# AutoSpiel.net
KiCad netlist of a schematic drawn in EAGLE
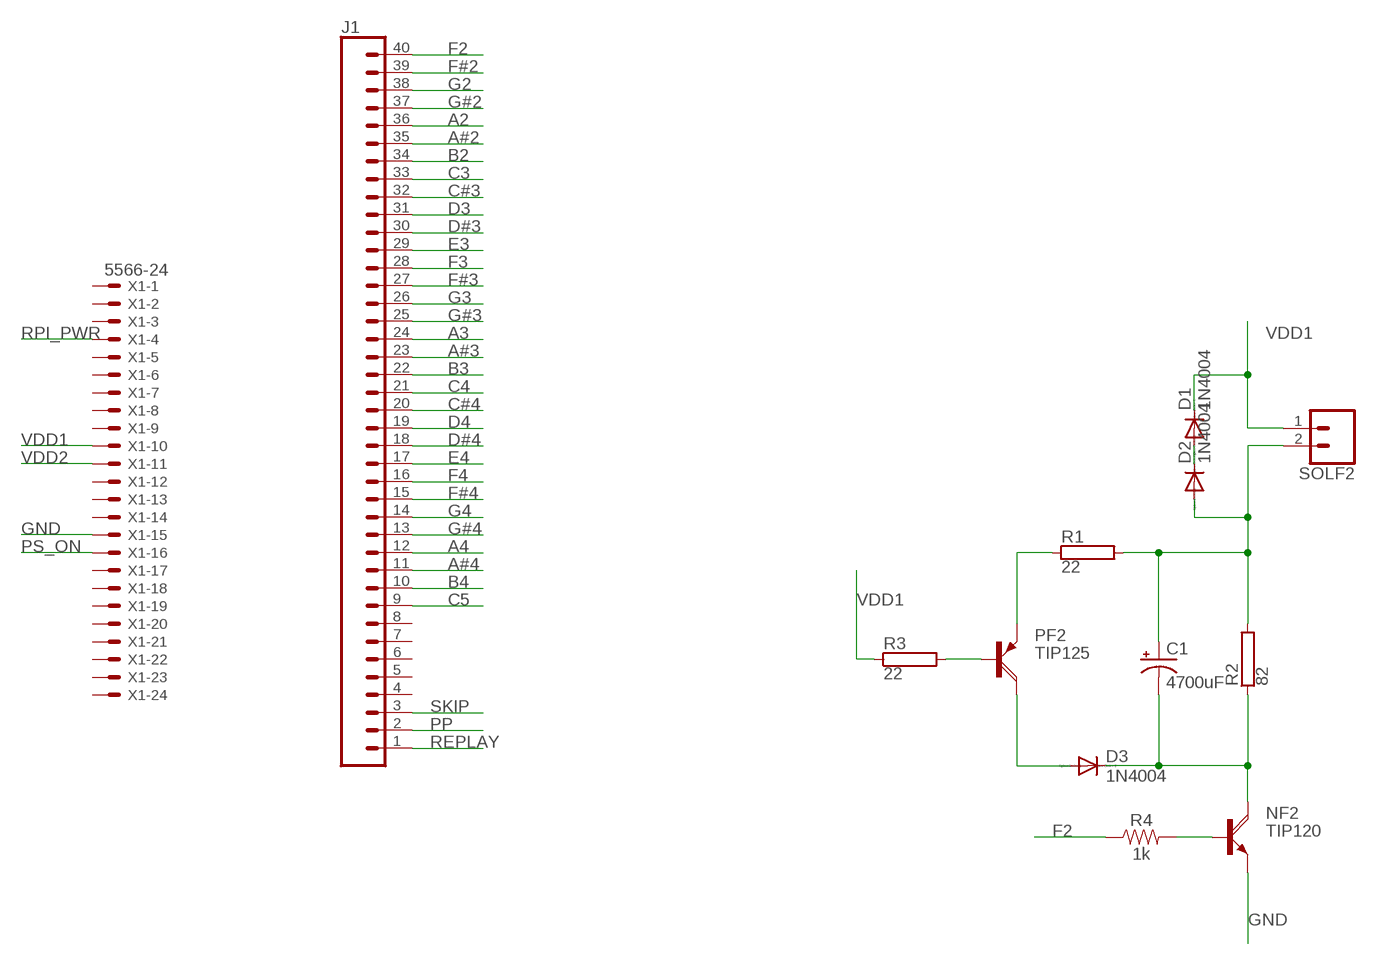
[diagram p0: schematic, sheet 1]

(export (version "E")
  (design (tool "Eeschema 10.0.6"))
  (components
    (comp (ref "C1")
      (value "4700uF")
      (footprint "eagle-import:E5-13")
      (libsource (lib "eagle-import") (part "CPOL-USE5-13"))
    )
    (comp (ref "D1")
      (value "1N4004")
      (footprint "eagle-import:DO41-10")
      (libsource (lib "eagle-import") (part "1N4004"))
    )
    (comp (ref "D2")
      (value "1N4004")
      (footprint "eagle-import:DO41-10")
      (libsource (lib "eagle-import") (part "1N4004"))
    )
    (comp (ref "D3")
      (value "1N4004")
      (footprint "eagle-import:DO41-10")
      (libsource (lib "eagle-import") (part "1N4004"))
    )
    (comp (ref "J1")
      (value "CONN_40")
      (footprint "eagle-import:1X40")
      (libsource (lib "eagle-import") (part "CONN_40"))
    )
    (comp (ref "NF2")
      (value "TIP120")
      (footprint "eagle-import:TO220AH")
      (libsource (lib "eagle-import") (part "TIP120"))
    )
    (comp (ref "PF2")
      (value "TIP125")
      (footprint "eagle-import:TO220AH")
      (libsource (lib "eagle-import") (part "TIP125"))
    )
    (comp (ref "R1")
      (value "22")
      (footprint "eagle-import:AC01")
      (libsource (lib "eagle-import") (part "RAC01"))
    )
    (comp (ref "R2")
      (value "82")
      (footprint "eagle-import:AC01")
      (libsource (lib "eagle-import") (part "RAC01"))
    )
    (comp (ref "R3")
      (value "22")
      (footprint "eagle-import:AC01")
      (libsource (lib "eagle-import") (part "RAC01"))
    )
    (comp (ref "R4")
      (value "1k")
      (footprint "eagle-import:AXIAL-0.3-KIT")
      (libsource (lib "eagle-import") (part "1KOHM-HORIZ_KIT-1/4W-5%"))
    )
    (comp (ref "SOLF2")
      (value "CONN_02PTH4")
      (footprint "eagle-import:1X02_XTRA_BIG")
      (libsource (lib "eagle-import") (part "CONN_02PTH4"))
    )
    (comp (ref "X1")
      (value "5566-24")
      (footprint "eagle-import:5566-24")
      (fields (field (name "MF") "MOLEX"))
      (libsource (lib "eagle-import") (part "5566-24"))
    )
  )
  (nets
    (net (code "1") (name "/A#2") (class "Default")
      (node (ref "J1") (pin "35") (pinfunction "35_35") (pintype "passive"))
    )
    (net (code "2") (name "/A#3") (class "Default")
      (node (ref "J1") (pin "23") (pinfunction "23_23") (pintype "passive"))
    )
    (net (code "3") (name "/A#4") (class "Default")
      (node (ref "J1") (pin "11") (pinfunction "11_11") (pintype "passive"))
    )
    (net (code "4") (name "/A2") (class "Default")
      (node (ref "J1") (pin "36") (pinfunction "36_36") (pintype "passive"))
    )
    (net (code "5") (name "/A3") (class "Default")
      (node (ref "J1") (pin "24") (pinfunction "24_24") (pintype "passive"))
    )
    (net (code "6") (name "/A4") (class "Default")
      (node (ref "J1") (pin "12") (pinfunction "12_12") (pintype "passive"))
    )
    (net (code "7") (name "/B2") (class "Default")
      (node (ref "J1") (pin "34") (pinfunction "34_34") (pintype "passive"))
    )
    (net (code "8") (name "/B3") (class "Default")
      (node (ref "J1") (pin "22") (pinfunction "22_22") (pintype "passive"))
    )
    (net (code "9") (name "/B4") (class "Default")
      (node (ref "J1") (pin "10") (pinfunction "10_10") (pintype "passive"))
    )
    (net (code "10") (name "/C#3") (class "Default")
      (node (ref "J1") (pin "32") (pinfunction "32_32") (pintype "passive"))
    )
    (net (code "11") (name "/C#4") (class "Default")
      (node (ref "J1") (pin "20") (pinfunction "20_20") (pintype "passive"))
    )
    (net (code "12") (name "/C3") (class "Default")
      (node (ref "J1") (pin "33") (pinfunction "33_33") (pintype "passive"))
    )
    (net (code "13") (name "/C4") (class "Default")
      (node (ref "J1") (pin "21") (pinfunction "21_21") (pintype "passive"))
    )
    (net (code "14") (name "/C5") (class "Default")
      (node (ref "J1") (pin "9") (pinfunction "9_9") (pintype "passive"))
    )
    (net (code "15") (name "/D#3") (class "Default")
      (node (ref "J1") (pin "30") (pinfunction "30_30") (pintype "passive"))
    )
    (net (code "16") (name "/D#4") (class "Default")
      (node (ref "J1") (pin "18") (pinfunction "18_18") (pintype "passive"))
    )
    (net (code "17") (name "/D3") (class "Default")
      (node (ref "J1") (pin "31") (pinfunction "31_31") (pintype "passive"))
    )
    (net (code "18") (name "/D4") (class "Default")
      (node (ref "J1") (pin "19") (pinfunction "19_19") (pintype "passive"))
    )
    (net (code "19") (name "/E3") (class "Default")
      (node (ref "J1") (pin "29") (pinfunction "29_29") (pintype "passive"))
    )
    (net (code "20") (name "/E4") (class "Default")
      (node (ref "J1") (pin "17") (pinfunction "17_17") (pintype "passive"))
    )
    (net (code "21") (name "/F#2") (class "Default")
      (node (ref "J1") (pin "39") (pinfunction "39_39") (pintype "passive"))
    )
    (net (code "22") (name "/F#3") (class "Default")
      (node (ref "J1") (pin "27") (pinfunction "27_27") (pintype "passive"))
    )
    (net (code "23") (name "/F#4") (class "Default")
      (node (ref "J1") (pin "15") (pinfunction "15_15") (pintype "passive"))
    )
    (net (code "24") (name "/F2") (class "Default")
      (node (ref "J1") (pin "40") (pinfunction "40_40") (pintype "passive"))
      (node (ref "R4") (pin "P$1") (pinfunction "1_P$1") (pintype "passive"))
    )
    (net (code "25") (name "/F3") (class "Default")
      (node (ref "J1") (pin "28") (pinfunction "28_28") (pintype "passive"))
    )
    (net (code "26") (name "/F4") (class "Default")
      (node (ref "J1") (pin "16") (pinfunction "16_16") (pintype "passive"))
    )
    (net (code "27") (name "/G#2") (class "Default")
      (node (ref "J1") (pin "37") (pinfunction "37_37") (pintype "passive"))
    )
    (net (code "28") (name "/G#3") (class "Default")
      (node (ref "J1") (pin "25") (pinfunction "25_25") (pintype "passive"))
    )
    (net (code "29") (name "/G#4") (class "Default")
      (node (ref "J1") (pin "13") (pinfunction "13_13") (pintype "passive"))
    )
    (net (code "30") (name "/G2") (class "Default")
      (node (ref "J1") (pin "38") (pinfunction "38_38") (pintype "passive"))
    )
    (net (code "31") (name "/G3") (class "Default")
      (node (ref "J1") (pin "26") (pinfunction "26_26") (pintype "passive"))
    )
    (net (code "32") (name "/G4") (class "Default")
      (node (ref "J1") (pin "14") (pinfunction "14_14") (pintype "passive"))
    )
    (net (code "33") (name "/GND") (class "Default")
      (node (ref "NF2") (pin "E") (pinfunction "E_E") (pintype "passive"))
      (node (ref "X1") (pin "15") (pinfunction "S_15") (pintype "passive"))
    )
    (net (code "34") (name "/PP") (class "Default")
      (node (ref "J1") (pin "2") (pinfunction "2_2") (pintype "passive"))
    )
    (net (code "35") (name "/PS_ON") (class "Default")
      (node (ref "X1") (pin "16") (pinfunction "S_16") (pintype "passive"))
    )
    (net (code "36") (name "/REPLAY") (class "Default")
      (node (ref "J1") (pin "1") (pinfunction "1_1") (pintype "passive"))
    )
    (net (code "37") (name "/RPI_PWR") (class "Default")
      (node (ref "X1") (pin "4") (pinfunction "S_4") (pintype "passive"))
    )
    (net (code "38") (name "/SKIP") (class "Default")
      (node (ref "J1") (pin "3") (pinfunction "3_3") (pintype "passive"))
    )
    (net (code "39") (name "/VDD1") (class "Default")
      (node (ref "D1") (pin "C") (pinfunction "C_C") (pintype "passive"))
      (node (ref "R3") (pin "1") (pinfunction "1_1") (pintype "passive"))
      (node (ref "SOLF2") (pin "1") (pinfunction "1_1") (pintype "passive"))
      (node (ref "X1") (pin "10") (pinfunction "S_10") (pintype "passive"))
    )
    (net (code "40") (name "/VDD2") (class "Default")
      (node (ref "X1") (pin "11") (pinfunction "S_11") (pintype "passive"))
    )
    (net (code "41") (name "Net-(C1-Pad+)") (class "Default")
      (node (ref "C1") (pin "+") (pinfunction "+_+") (pintype "passive"))
      (node (ref "D2") (pin "A") (pinfunction "A_A") (pintype "passive"))
      (node (ref "R1") (pin "2") (pinfunction "2_2") (pintype "passive"))
      (node (ref "R2") (pin "2") (pinfunction "2_2") (pintype "passive"))
      (node (ref "SOLF2") (pin "2") (pinfunction "2_2") (pintype "passive"))
    )
    (net (code "42") (name "Net-(C1-Pad-)") (class "Default")
      (node (ref "C1") (pin "-") (pinfunction "-_-") (pintype "passive"))
      (node (ref "D3") (pin "C") (pinfunction "C_C") (pintype "passive"))
      (node (ref "NF2") (pin "C") (pinfunction "C_C") (pintype "passive"))
      (node (ref "R2") (pin "1") (pinfunction "1_1") (pintype "passive"))
    )
    (net (code "43") (name "Net-(D1-PadA)") (class "Default")
      (node (ref "D1") (pin "A") (pinfunction "A_A") (pintype "passive"))
      (node (ref "D2") (pin "C") (pinfunction "C_C") (pintype "passive"))
    )
    (net (code "44") (name "Net-(D3-PadA)") (class "Default")
      (node (ref "D3") (pin "A") (pinfunction "A_A") (pintype "passive"))
      (node (ref "PF2") (pin "C") (pinfunction "C_C") (pintype "passive"))
    )
    (net (code "45") (name "Net-(PF2-PadB)") (class "Default")
      (node (ref "PF2") (pin "B") (pinfunction "B_B") (pintype "passive"))
      (node (ref "R3") (pin "2") (pinfunction "2_2") (pintype "passive"))
    )
    (net (code "46") (name "Net-(PF2-PadE)") (class "Default")
      (node (ref "PF2") (pin "E") (pinfunction "E_E") (pintype "passive"))
      (node (ref "R1") (pin "1") (pinfunction "1_1") (pintype "passive"))
    )
    (net (code "47") (name "Net-(R4-2)") (class "Default")
      (node (ref "NF2") (pin "B") (pinfunction "B_B") (pintype "passive"))
      (node (ref "R4") (pin "P$2") (pinfunction "2_P$2") (pintype "passive"))
    )
    (net (code "48") (name "unconnected-(J1-Pad4)") (class "Default")
      (node (ref "J1") (pin "4") (pinfunction "4_4") (pintype "passive"))
    )
    (net (code "49") (name "unconnected-(J1-Pad5)") (class "Default")
      (node (ref "J1") (pin "5") (pinfunction "5_5") (pintype "passive"))
    )
    (net (code "50") (name "unconnected-(J1-Pad6)") (class "Default")
      (node (ref "J1") (pin "6") (pinfunction "6_6") (pintype "passive"))
    )
    (net (code "51") (name "unconnected-(J1-Pad7)") (class "Default")
      (node (ref "J1") (pin "7") (pinfunction "7_7") (pintype "passive"))
    )
    (net (code "52") (name "unconnected-(J1-Pad8)") (class "Default")
      (node (ref "J1") (pin "8") (pinfunction "8_8") (pintype "passive"))
    )
    (net (code "53") (name "unconnected-(X1A-S-Pad1)") (class "Default")
      (node (ref "X1") (pin "1") (pinfunction "S_1") (pintype "passive"))
    )
    (net (code "54") (name "unconnected-(X1D-S-Pad12)") (class "Default")
      (node (ref "X1") (pin "12") (pinfunction "S_12") (pintype "passive"))
    )
    (net (code "55") (name "unconnected-(X1E-S-Pad13)") (class "Default")
      (node (ref "X1") (pin "13") (pinfunction "S_13") (pintype "passive"))
    )
    (net (code "56") (name "unconnected-(X1F-S-Pad14)") (class "Default")
      (node (ref "X1") (pin "14") (pinfunction "S_14") (pintype "passive"))
    )
    (net (code "57") (name "unconnected-(X1I-S-Pad17)") (class "Default")
      (node (ref "X1") (pin "17") (pinfunction "S_17") (pintype "passive"))
    )
    (net (code "58") (name "unconnected-(X1J-S-Pad18)") (class "Default")
      (node (ref "X1") (pin "18") (pinfunction "S_18") (pintype "passive"))
    )
    (net (code "59") (name "unconnected-(X1K-S-Pad19)") (class "Default")
      (node (ref "X1") (pin "19") (pinfunction "S_19") (pintype "passive"))
    )
    (net (code "60") (name "unconnected-(X1L-S-Pad2)") (class "Default")
      (node (ref "X1") (pin "2") (pinfunction "S_2") (pintype "passive"))
    )
    (net (code "61") (name "unconnected-(X1M-S-Pad20)") (class "Default")
      (node (ref "X1") (pin "20") (pinfunction "S_20") (pintype "passive"))
    )
    (net (code "62") (name "unconnected-(X1N-S-Pad21)") (class "Default")
      (node (ref "X1") (pin "21") (pinfunction "S_21") (pintype "passive"))
    )
    (net (code "63") (name "unconnected-(X1O-S-Pad22)") (class "Default")
      (node (ref "X1") (pin "22") (pinfunction "S_22") (pintype "passive"))
    )
    (net (code "64") (name "unconnected-(X1P-S-Pad23)") (class "Default")
      (node (ref "X1") (pin "23") (pinfunction "S_23") (pintype "passive"))
    )
    (net (code "65") (name "unconnected-(X1Q-S-Pad24)") (class "Default")
      (node (ref "X1") (pin "24") (pinfunction "S_24") (pintype "passive"))
    )
    (net (code "66") (name "unconnected-(X1R-S-Pad3)") (class "Default")
      (node (ref "X1") (pin "3") (pinfunction "S_3") (pintype "passive"))
    )
    (net (code "67") (name "unconnected-(X1T-S-Pad5)") (class "Default")
      (node (ref "X1") (pin "5") (pinfunction "S_5") (pintype "passive"))
    )
    (net (code "68") (name "unconnected-(X1U-S-Pad6)") (class "Default")
      (node (ref "X1") (pin "6") (pinfunction "S_6") (pintype "passive"))
    )
    (net (code "69") (name "unconnected-(X1V-S-Pad7)") (class "Default")
      (node (ref "X1") (pin "7") (pinfunction "S_7") (pintype "passive"))
    )
    (net (code "70") (name "unconnected-(X1W-S-Pad8)") (class "Default")
      (node (ref "X1") (pin "8") (pinfunction "S_8") (pintype "passive"))
    )
    (net (code "71") (name "unconnected-(X1X-S-Pad9)") (class "Default")
      (node (ref "X1") (pin "9") (pinfunction "S_9") (pintype "passive"))
    )
  )
)
